# Power_Supply.net
KiCad netlist of a schematic drawn in Altium Designer
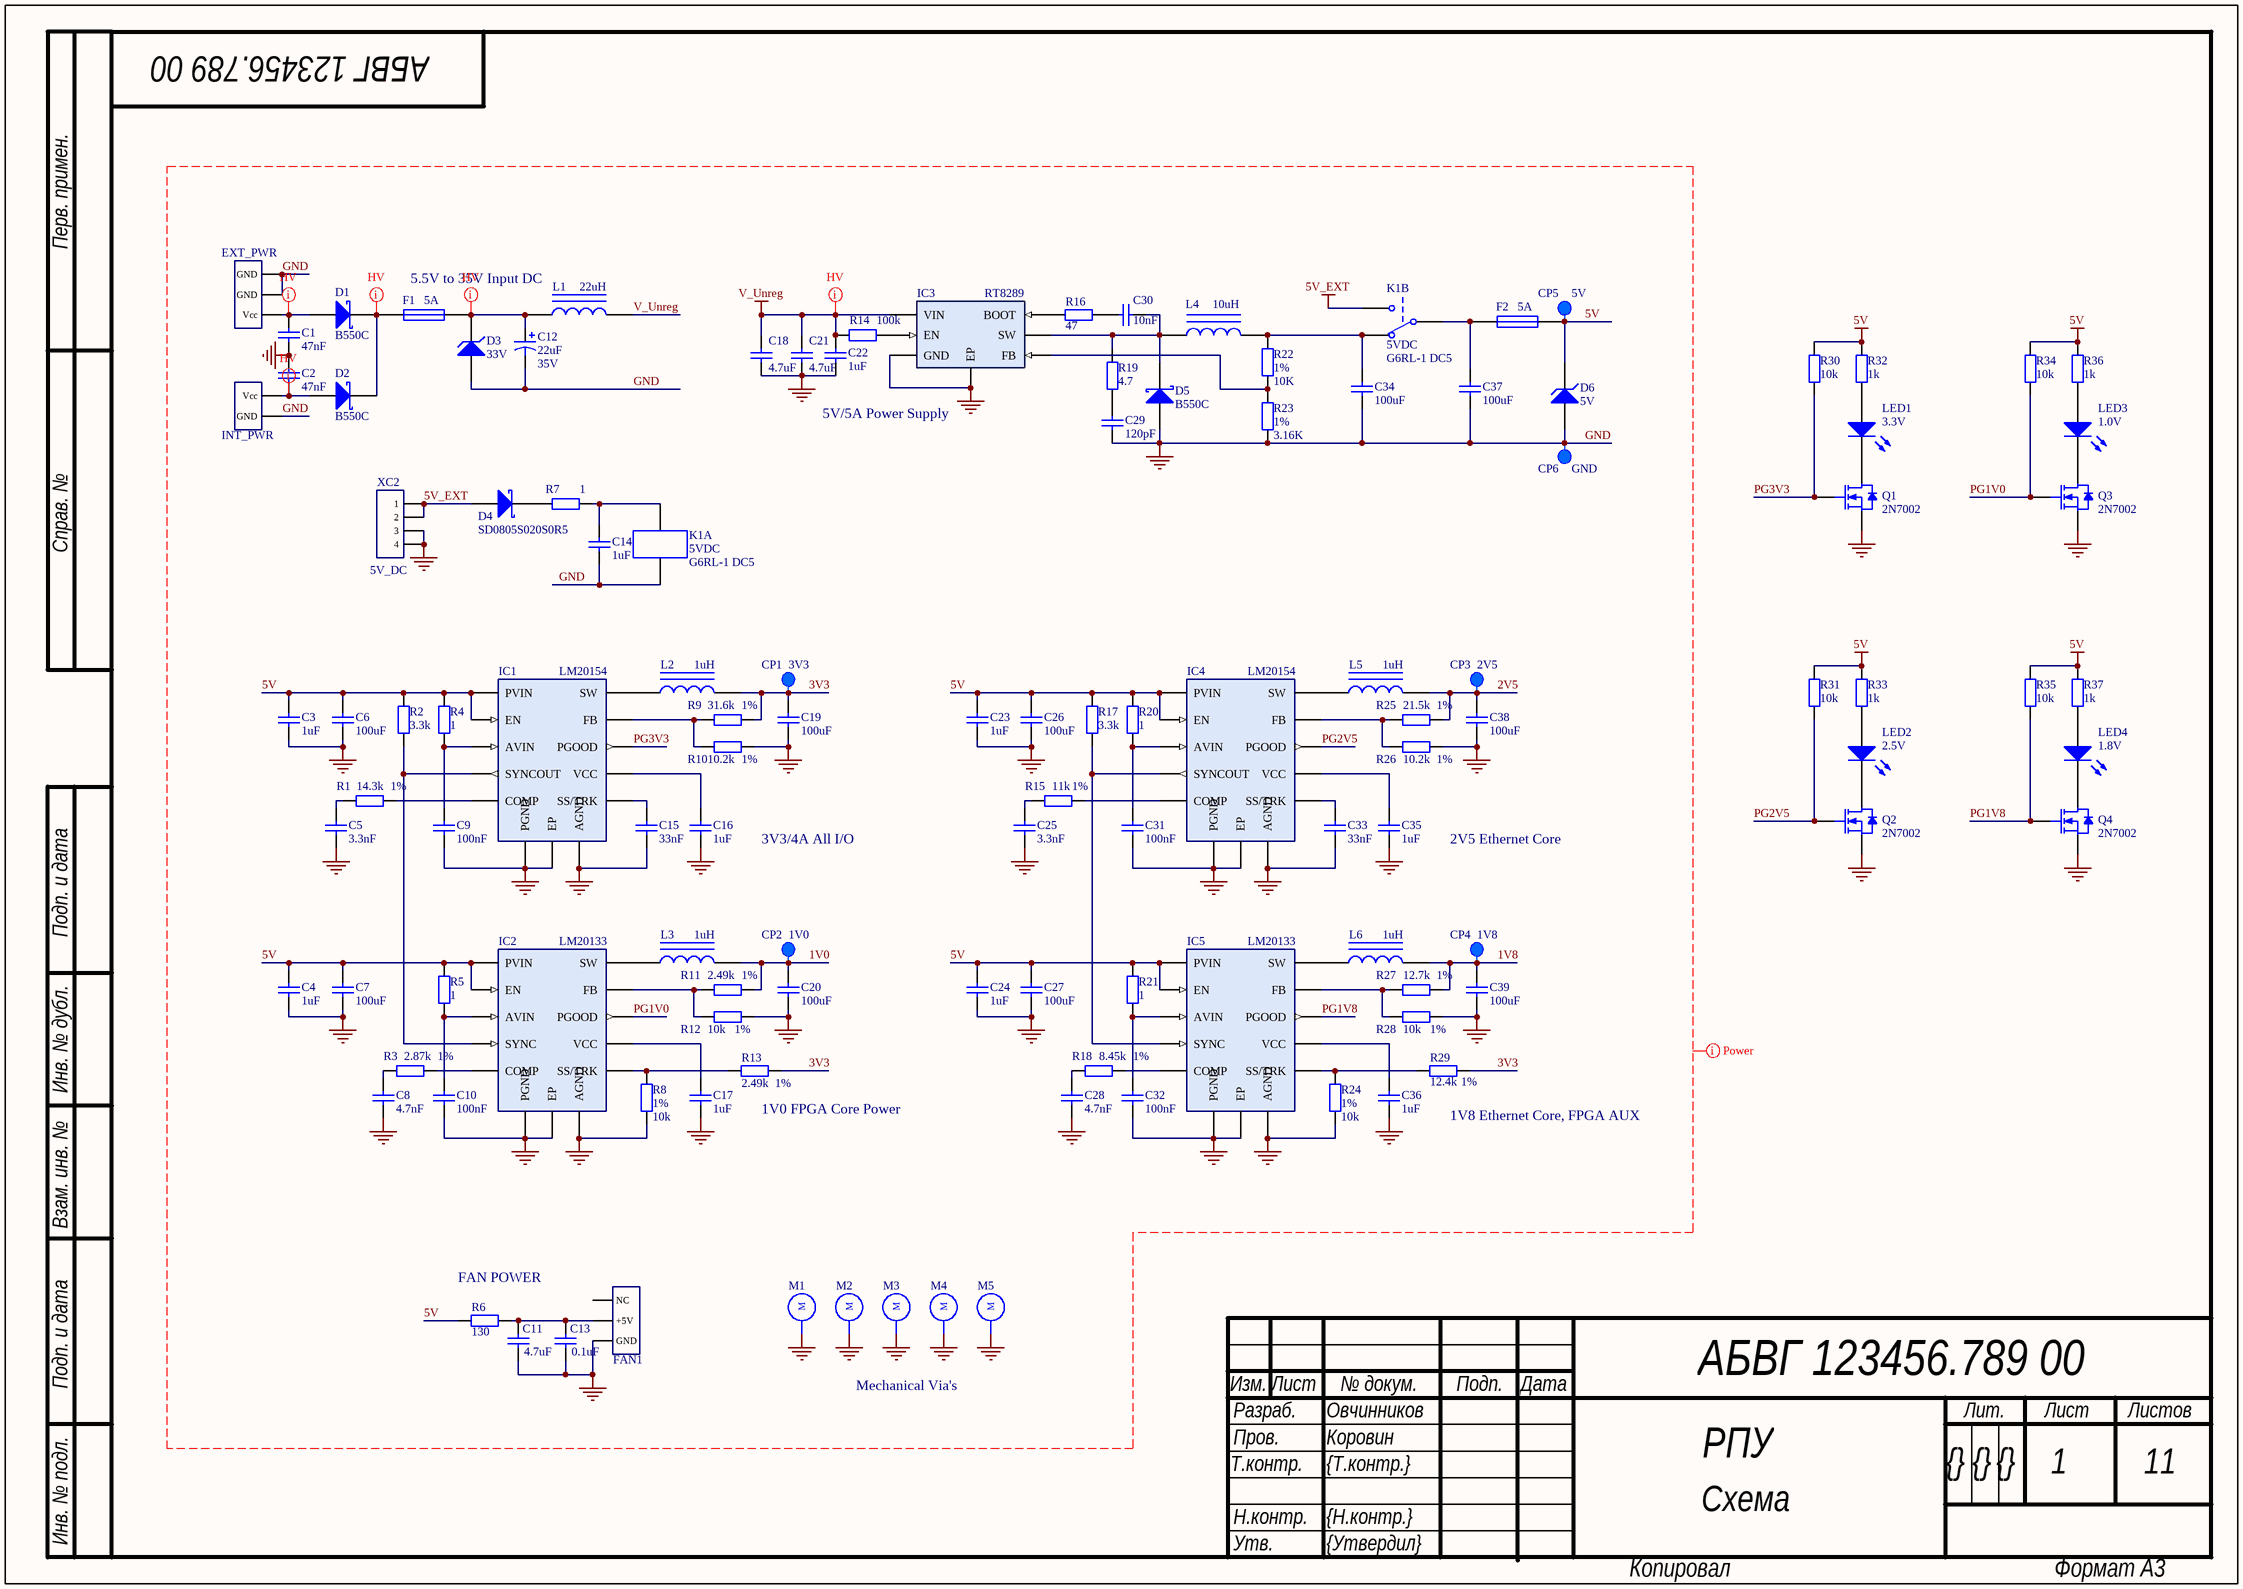
[diagram p0: Power_Supply.SchDoc]

(export (version "E")
  (design (tool "Eeschema 10.0.6"))
  (components
    (comp (ref "C1")
      (value "47nF")
      (footprint "C0805")
      (description "Cer Cap Small")
      (fields (field (name "MANUFACTURER") "Murata") (field (name "VOLTAGE") "50V"))
      (libsource (lib "USRP2_Clone") (part "Cer Cap"))
    )
    (comp (ref "C2")
      (value "47nF")
      (footprint "C0805")
      (description "Cer Cap Small")
      (fields (field (name "MANUFACTURER") "Murata") (field (name "VOLTAGE") "50V"))
      (libsource (lib "USRP2_Clone") (part "Cer Cap"))
    )
    (comp (ref "C3")
      (value "1uF")
      (footprint "C0805")
      (description "Cer Cap Small")
      (fields (field (name "MANUFACTURER") "Murata") (field (name "VOLTAGE") "16V"))
      (libsource (lib "USRP2_Clone") (part "Cer Cap"))
    )
    (comp (ref "C4")
      (value "1uF")
      (footprint "C0805")
      (description "Cer Cap Small")
      (fields (field (name "MANUFACTURER") "Murata") (field (name "VOLTAGE") "16V"))
      (libsource (lib "USRP2_Clone") (part "Cer Cap"))
    )
    (comp (ref "C5")
      (value "3.3nF")
      (footprint "C0603")
      (description "Cer Cap Small")
      (fields (field (name "MANUFACTURER") "Murata") (field (name "VOLTAGE") "25V"))
      (libsource (lib "USRP2_Clone") (part "Cer Cap"))
    )
    (comp (ref "C6")
      (value "100uF")
      (footprint "C1210")
      (description "Cer Cap Large")
      (fields (field (name "MANUFACTURER") "Murata") (field (name "TOLERANCE") "20%"))
      (libsource (lib "USRP2_Clone") (part "Cap uF"))
    )
    (comp (ref "C7")
      (value "100uF")
      (footprint "C1210")
      (description "Cer Cap Large")
      (fields (field (name "MANUFACTURER") "Murata") (field (name "TOLERANCE") "20%"))
      (libsource (lib "USRP2_Clone") (part "Cap uF"))
    )
    (comp (ref "C8")
      (value "4.7nF")
      (footprint "C0603")
      (description "Cer Cap Small")
      (fields (field (name "MANUFACTURER") "Murata") (field (name "VOLTAGE") "25V"))
      (libsource (lib "USRP2_Clone") (part "Cer Cap"))
    )
    (comp (ref "C9")
      (value "100nF")
      (footprint "C0603")
      (description "Cer Cap Small")
      (fields (field (name "MANUFACTURER") "Murata") (field (name "VOLTAGE") "16V"))
      (libsource (lib "USRP2_Clone") (part "Cer Cap"))
    )
    (comp (ref "C10")
      (value "100nF")
      (footprint "C0603")
      (description "Cer Cap Small")
      (fields (field (name "MANUFACTURER") "Murata") (field (name "VOLTAGE") "16V"))
      (libsource (lib "") (part "Cer Cap_1"))
    )
    (comp (ref "C11")
      (value "4.7uF")
      (footprint "C0805")
      (description "Cer Cap Small")
      (fields (field (name "MANUFACTURER") "Murata") (field (name "VOLTAGE") "16V"))
      (libsource (lib "USRP2_Clone") (part "Cer Cap"))
    )
    (comp (ref "C12")
      (value "22uF")
      (footprint "Tantalum_D")
      (description "Tantalum Polarity Cap")
      (fields
        (field (name "MANUFACTURER") "Tecap")
        (field (name "TOLERANCE") "20%")
        (field (name "VOLTAGE") "35V")
      )
      (libsource (lib "USRP2_Clone") (part "Tantalum Cap"))
    )
    (comp (ref "C13")
      (value "0.1uF")
      (footprint "C0805")
      (description "Cer Cap Small")
      (fields (field (name "MANUFACTURER") "Murata") (field (name "VOLTAGE") "16V"))
      (libsource (lib "USRP2_Clone") (part "Cer Cap"))
    )
    (comp (ref "C14")
      (value "1uF")
      (footprint "C0805")
      (description "Cer Cap Small")
      (fields (field (name "MANUFACTURER") "Murata") (field (name "VOLTAGE") "16V"))
      (libsource (lib "USRP2_Clone") (part "Cer Cap"))
    )
    (comp (ref "C15")
      (value "33nF")
      (footprint "C0603")
      (description "Cer Cap Small")
      (fields (field (name "MANUFACTURER") "Murata") (field (name "VOLTAGE") "25V"))
      (libsource (lib "") (part "Cer Cap_1"))
    )
    (comp (ref "C16")
      (value "1uF")
      (footprint "C0603")
      (description "Cer Cap Small")
      (fields (field (name "MANUFACTURER") "Murata") (field (name "VOLTAGE") "6.3V"))
      (libsource (lib "") (part "Cer Cap_1"))
    )
    (comp (ref "C17")
      (value "1uF")
      (footprint "C0603")
      (description "Cer Cap Small")
      (fields (field (name "MANUFACTURER") "Murata") (field (name "VOLTAGE") "6.3V"))
      (libsource (lib "") (part "Cer Cap_1"))
    )
    (comp (ref "C18")
      (value "4.7uF")
      (footprint "C1206")
      (description "Cer Cap Small")
      (fields (field (name "MANUFACTURER") "Murata") (field (name "VOLTAGE") "50V"))
      (libsource (lib "") (part "Cer Cap_1"))
    )
    (comp (ref "C19")
      (value "100uF")
      (footprint "C1210")
      (description "Cer Cap Large")
      (fields (field (name "MANUFACTURER") "Murata") (field (name "TOLERANCE") "20%"))
      (libsource (lib "USRP2_Clone") (part "Cap uF"))
    )
    (comp (ref "C20")
      (value "100uF")
      (footprint "C1210")
      (description "Cer Cap Large")
      (fields (field (name "MANUFACTURER") "Murata") (field (name "TOLERANCE") "20%"))
      (libsource (lib "USRP2_Clone") (part "Cap uF"))
    )
    (comp (ref "C21")
      (value "4.7uF")
      (footprint "C1206")
      (description "Cer Cap Small")
      (fields (field (name "MANUFACTURER") "Murata") (field (name "VOLTAGE") "50V"))
      (libsource (lib "") (part "Cer Cap_1"))
    )
    (comp (ref "C22")
      (value "1uF")
      (footprint "C1206")
      (description "Cer Cap Small")
      (fields (field (name "MANUFACTURER") "Murata") (field (name "VOLTAGE") "50V"))
      (libsource (lib "") (part "Cer Cap_1"))
    )
    (comp (ref "C23")
      (value "1uF")
      (footprint "C0805")
      (description "Cer Cap Small")
      (fields (field (name "MANUFACTURER") "Murata") (field (name "VOLTAGE") "16V"))
      (libsource (lib "") (part "Cer Cap_1"))
    )
    (comp (ref "C24")
      (value "1uF")
      (footprint "C0805")
      (description "Cer Cap Small")
      (fields (field (name "MANUFACTURER") "Murata") (field (name "VOLTAGE") "16V"))
      (libsource (lib "") (part "Cer Cap_1"))
    )
    (comp (ref "C25")
      (value "3.3nF")
      (footprint "C0603")
      (description "Cer Cap Small")
      (fields (field (name "MANUFACTURER") "Murata") (field (name "VOLTAGE") "25V"))
      (libsource (lib "USRP2_Clone") (part "Cer Cap"))
    )
    (comp (ref "C26")
      (value "100uF")
      (footprint "C1210")
      (description "Cer Cap Large")
      (fields (field (name "MANUFACTURER") "Murata") (field (name "TOLERANCE") "20%"))
      (libsource (lib "USRP2_Clone") (part "Cap uF"))
    )
    (comp (ref "C27")
      (value "100uF")
      (footprint "C1210")
      (description "Cer Cap Large")
      (fields (field (name "MANUFACTURER") "Murata") (field (name "TOLERANCE") "20%"))
      (libsource (lib "USRP2_Clone") (part "Cap uF"))
    )
    (comp (ref "C28")
      (value "4.7nF")
      (footprint "C0603")
      (description "Cer Cap Small")
      (fields (field (name "MANUFACTURER") "Murata") (field (name "VOLTAGE") "25V"))
      (libsource (lib "USRP2_Clone") (part "Cer Cap"))
    )
    (comp (ref "C29")
      (value "120pF")
      (footprint "C0805")
      (description "Cer Cap Small")
      (fields (field (name "MANUFACTURER") "Murata") (field (name "VOLTAGE") "50V"))
      (libsource (lib "USRP2_Clone") (part "Cer Cap"))
    )
    (comp (ref "C30")
      (value "10nF")
      (footprint "C0805")
      (description "Cer Cap Small")
      (fields (field (name "MANUFACTURER") "Murata") (field (name "VOLTAGE") "50V"))
      (libsource (lib "") (part "Cer Cap_1"))
    )
    (comp (ref "C31")
      (value "100nF")
      (footprint "C0603")
      (description "Cer Cap Small")
      (fields (field (name "MANUFACTURER") "Murata") (field (name "VOLTAGE") "16V"))
      (libsource (lib "") (part "Cer Cap_1"))
    )
    (comp (ref "C32")
      (value "100nF")
      (footprint "C0603")
      (description "Cer Cap Small")
      (fields (field (name "MANUFACTURER") "Murata") (field (name "VOLTAGE") "16V"))
      (libsource (lib "") (part "Cer Cap_1"))
    )
    (comp (ref "C33")
      (value "33nF")
      (footprint "C0603")
      (description "Cer Cap Small")
      (fields (field (name "MANUFACTURER") "Murata") (field (name "VOLTAGE") "25V"))
      (libsource (lib "USRP2_Clone") (part "Cer Cap"))
    )
    (comp (ref "C34")
      (value "100uF")
      (footprint "C1210")
      (description "Cer Cap Large")
      (fields (field (name "MANUFACTURER") "Murata") (field (name "TOLERANCE") "20%"))
      (libsource (lib "USRP2_Clone") (part "Cap uF"))
    )
    (comp (ref "C35")
      (value "1uF")
      (footprint "C0603")
      (description "Cer Cap Small")
      (fields (field (name "MANUFACTURER") "Murata") (field (name "VOLTAGE") "6.3V"))
      (libsource (lib "") (part "Cer Cap_1"))
    )
    (comp (ref "C36")
      (value "1uF")
      (footprint "C0603")
      (description "Cer Cap Small")
      (fields (field (name "MANUFACTURER") "Murata") (field (name "VOLTAGE") "6.3V"))
      (libsource (lib "") (part "Cer Cap_1"))
    )
    (comp (ref "C37")
      (value "100uF")
      (footprint "C1210")
      (description "Cer Cap Large")
      (fields (field (name "MANUFACTURER") "Murata") (field (name "TOLERANCE") "20%"))
      (libsource (lib "") (part "Cap uF_1"))
    )
    (comp (ref "C38")
      (value "100uF")
      (footprint "C1210")
      (description "Cer Cap Large")
      (fields (field (name "MANUFACTURER") "Murata") (field (name "TOLERANCE") "20%"))
      (libsource (lib "") (part "Cap uF_1"))
    )
    (comp (ref "C39")
      (value "100uF")
      (footprint "C1210")
      (description "Cer Cap Large")
      (fields (field (name "MANUFACTURER") "Murata") (field (name "TOLERANCE") "20%"))
      (libsource (lib "") (part "Cap uF_1"))
    )
    (comp (ref "CP1")
      (value "3V3")
      (footprint "Control Point")
      (description "Control Point")
      (libsource (lib "USRP2_Clone") (part "Control Point"))
    )
    (comp (ref "CP2")
      (value "1V0")
      (footprint "Control Point")
      (description "Control Point")
      (libsource (lib "USRP2_Clone") (part "Control Point"))
    )
    (comp (ref "CP3")
      (value "2V5")
      (footprint "Control Point")
      (description "Control Point")
      (libsource (lib "USRP2_Clone") (part "Control Point"))
    )
    (comp (ref "CP4")
      (value "1V8")
      (footprint "Control Point")
      (description "Control Point")
      (libsource (lib "USRP2_Clone") (part "Control Point"))
    )
    (comp (ref "CP5")
      (value "5V")
      (footprint "Control Point")
      (description "Control Point")
      (libsource (lib "USRP2_Clone") (part "Control Point"))
    )
    (comp (ref "CP6")
      (value "GND")
      (footprint "Control Point")
      (description "Control Point")
      (libsource (lib "USRP2_Clone") (part "Control Point"))
    )
    (comp (ref "D1")
      (value "B550C")
      (footprint "Diode_SMC")
      (description "Schottky Diode")
      (fields (field (name "NAME") "B550C"))
      (libsource (lib "USRP2_Clone") (part "B550C"))
    )
    (comp (ref "D2")
      (value "B550C")
      (footprint "Diode_SMC")
      (description "Schottky Diode")
      (fields (field (name "NAME") "B550C"))
      (libsource (lib "USRP2_Clone") (part "B550C"))
    )
    (comp (ref "D3")
      (value "Supressor")
      (footprint "SMF")
      (description "33V Supressor")
      (fields (field (name "POWER") "200W") (field (name "VOLTAGE") "33V"))
      (libsource (lib "USRP2_Clone") (part "Supressor"))
    )
    (comp (ref "D4")
      (value "D Schottky")
      (footprint "SD0805")
      (description "Schottky Diode SMD")
      (fields
        (field (name "VOLTAGE") "20V")
        (field (name "NAME") "SD0805S020S0R5")
        (field (name "MANUFACTURER") "AVX Corporation")
      )
      (libsource (lib "USRP2_Clone") (part "D Schottky"))
    )
    (comp (ref "D5")
      (value "B550C")
      (footprint "Diode_SMC")
      (description "Schottky Diode")
      (fields (field (name "NAME") "B550C"))
      (libsource (lib "USRP2_Clone") (part "B550C"))
    )
    (comp (ref "D6")
      (value "Supressor")
      (footprint "SMF")
      (fields (field (name "POWER") "200W") (field (name "VOLTAGE") "5V"))
      (libsource (lib "USRP2_Clone") (part "Supressor"))
    )
    (comp (ref "DC_PWR1")
      (value "EXT_PWR")
      (footprint "DC_CONNECTOR")
      (description "DC Power Connector 6mm")
      (fields (field (name "VOLTAGE") "12V"))
      (libsource (lib "USRP2_Clone") (part "DC_Connector"))
    )
    (comp (ref "F1")
      (value "Fuse")
      (footprint "Fuse")
      (description "Chip SMD Fuse")
      (fields (field (name "VOLTAGE") "125V") (field (name "CURRENT") "5A"))
      (libsource (lib "") (part "Fuse_1"))
    )
    (comp (ref "F2")
      (value "Fuse")
      (footprint "Fuse")
      (description "Chip SMD Fuse")
      (fields (field (name "VOLTAGE") "125V") (field (name "CURRENT") "5A"))
      (libsource (lib "USRP2_Clone") (part "Fuse"))
    )
    (comp (ref "FAN1")
      (value "FAN")
      (footprint "FAN_HDR")
      (description "FAN Connector")
      (fields (field (name "VOLTAGE") "12V"))
      (libsource (lib "USRP2_Clone") (part "FAN Connector"))
    )
    (comp (ref "IC1")
      (value "LM20154")
      (footprint "LM201xx")
      (description "Synchrous Buck Regulator")
      (libsource (lib "USRP2_Clone") (part "LM20154"))
    )
    (comp (ref "IC2")
      (value "LM20133")
      (footprint "LM201xx")
      (description "Synchronous Buck Regulator")
      (libsource (lib "USRP2_Clone") (part "LM20133"))
    )
    (comp (ref "IC3")
      (value "RT8289")
      (footprint "RT8289")
      (description "Step-Down Converter")
      (fields (field (name "VOLTAGE") "32V"))
      (libsource (lib "USRP2_Clone") (part "RT8289"))
    )
    (comp (ref "IC4")
      (value "LM20154")
      (footprint "LM201xx")
      (description "Synchrous Buck Regulator")
      (libsource (lib "USRP2_Clone") (part "LM20154"))
    )
    (comp (ref "IC5")
      (value "LM20133")
      (footprint "LM201xx")
      (description "Synchronous Buck Regulator")
      (libsource (lib "USRP2_Clone") (part "LM20133"))
    )
    (comp (ref "K1")
      (value "5VDC")
      (footprint "G6RL")
      (description "Single-Pole Dual-Throw Relay")
      (fields (field (name "MANUFACTURER") "Omron") (field (name "NAME") "G6RL-1 DC5"))
      (libsource (lib "USRP2_Clone") (part "Relay-SPDT_G6RL"))
    )
    (comp (ref "L1")
      (value "22uH")
      (footprint "XAL6060-223")
      (description "Magnetic-Core Inductor")
      (fields (field (name "TOLERANCE") "±30%") (field (name "MANUFACTURER") "Coilcraft"))
      (libsource (lib "USRP2_Clone") (part "Inductor Power"))
    )
    (comp (ref "L2")
      (value "1uH")
      (footprint "Coilcraft MSS1038")
      (description "Magnetic-Core Inductor")
      (fields (field (name "TOLERANCE") "±30%") (field (name "MANUFACTURER") "Coilcraft"))
      (libsource (lib "USRP2_Clone") (part "Inductor Power"))
    )
    (comp (ref "L3")
      (value "1uH")
      (footprint "Coilcraft MSS1038")
      (description "Magnetic-Core Inductor")
      (fields (field (name "TOLERANCE") "±30%") (field (name "MANUFACTURER") "Coilcraft"))
      (libsource (lib "USRP2_Clone") (part "Inductor Power"))
    )
    (comp (ref "L4")
      (value "10uH")
      (footprint "Coilcraft MSS1048")
      (description "Magnetic-Core Inductor")
      (fields (field (name "TOLERANCE") "±30%") (field (name "MANUFACTURER") "Coilcraft"))
      (libsource (lib "USRP2_Clone") (part "Inductor Power"))
    )
    (comp (ref "L5")
      (value "1uH")
      (footprint "Coilcraft MSS1038")
      (description "Magnetic-Core Inductor")
      (fields (field (name "TOLERANCE") "±30%") (field (name "MANUFACTURER") "Coilcraft"))
      (libsource (lib "USRP2_Clone") (part "Inductor Power"))
    )
    (comp (ref "L6")
      (value "1uH")
      (footprint "Coilcraft MSS1038")
      (description "Magnetic-Core Inductor")
      (fields (field (name "TOLERANCE") "±30%") (field (name "MANUFACTURER") "Coilcraft"))
      (libsource (lib "USRP2_Clone") (part "Inductor Power"))
    )
    (comp (ref "LED1")
      (value "3.3V")
      (footprint "LED_0402_Blue")
      (description "Typical RED, GREEN, YELLOW, AMBER GaAs LED")
      (fields (field (name "MANUFACTURER") "Kingbright"))
      (libsource (lib "USRP2_Clone") (part "LED"))
    )
    (comp (ref "LED2")
      (value "2.5V")
      (footprint "LED_0402_Blue")
      (description "Typical RED, GREEN, YELLOW, AMBER GaAs LED")
      (fields (field (name "MANUFACTURER") "Kingbright"))
      (libsource (lib "USRP2_Clone") (part "LED"))
    )
    (comp (ref "LED3")
      (value "1.0V")
      (footprint "LED_0402_Blue")
      (description "Typical RED, GREEN, YELLOW, AMBER GaAs LED")
      (fields (field (name "MANUFACTURER") "Kingbright"))
      (libsource (lib "USRP2_Clone") (part "LED"))
    )
    (comp (ref "LED4")
      (value "1.8V")
      (footprint "LED_0402_Blue")
      (description "Typical RED, GREEN, YELLOW, AMBER GaAs LED")
      (fields (field (name "MANUFACTURER") "Kingbright"))
      (libsource (lib "USRP2_Clone") (part "LED"))
    )
    (comp (ref "M1")
      (value "Via")
      (footprint "Mechanical_Via")
      (description "Mechanical Via")
      (libsource (lib "USRP2_Clone") (part "Mechanical_Via"))
    )
    (comp (ref "M2")
      (value "Via")
      (footprint "Mechanical_Via")
      (description "Mechanical Via")
      (libsource (lib "USRP2_Clone") (part "Mechanical_Via"))
    )
    (comp (ref "M3")
      (value "Via")
      (footprint "Mechanical_Via")
      (description "Mechanical Via")
      (libsource (lib "USRP2_Clone") (part "Mechanical_Via"))
    )
    (comp (ref "M4")
      (value "Via")
      (footprint "Mechanical_Via")
      (description "Mechanical Via")
      (libsource (lib "USRP2_Clone") (part "Mechanical_Via"))
    )
    (comp (ref "M5")
      (value "Via")
      (footprint "Mechanical_Via")
      (description "Mechanical Via")
      (libsource (lib "USRP2_Clone") (part "Mechanical_Via"))
    )
    (comp (ref "Q1")
      (value "2N7002")
      (footprint "SOT-23")
      (description "N-Channel MOSFET 2N7002")
      (fields (field (name "VOLTAGE") "60V"))
      (libsource (lib "USRP2_Clone") (part "2N7002"))
    )
    (comp (ref "Q2")
      (value "2N7002")
      (footprint "SOT-23")
      (description "N-Channel MOSFET 2N7002")
      (fields (field (name "VOLTAGE") "60V"))
      (libsource (lib "USRP2_Clone") (part "2N7002"))
    )
    (comp (ref "Q3")
      (value "2N7002")
      (footprint "SOT-23")
      (description "N-Channel MOSFET 2N7002")
      (fields (field (name "VOLTAGE") "60V"))
      (libsource (lib "USRP2_Clone") (part "2N7002"))
    )
    (comp (ref "Q4")
      (value "2N7002")
      (footprint "SOT-23")
      (description "N-Channel MOSFET 2N7002")
      (fields (field (name "VOLTAGE") "60V"))
      (libsource (lib "USRP2_Clone") (part "2N7002"))
    )
    (comp (ref "R1")
      (value "14.3k")
      (footprint "R0603")
      (description "Resistor")
      (fields
        (field (name "TOLERANCE") "1%")
        (field (name "POWER") "0.062 Wt")
        (field (name "Comment") "Res")
      )
      (libsource (lib "") (part "Res_2"))
    )
    (comp (ref "R2")
      (value "3.3k")
      (footprint "R0603")
      (description "Resistor")
      (fields (field (name "TOLERANCE") "5%") (field (name "POWER") "0.062 Wt"))
      (libsource (lib "") (part "Res_5"))
    )
    (comp (ref "R3")
      (value "2.87k")
      (footprint "R0603")
      (description "Resistor")
      (fields
        (field (name "TOLERANCE") "1%")
        (field (name "POWER") "0.062 Wt")
        (field (name "Comment") "Res")
      )
      (libsource (lib "") (part "Res_2"))
    )
    (comp (ref "R4")
      (value "1")
      (footprint "R0603")
      (description "Resistor")
      (fields (field (name "TOLERANCE") "5%") (field (name "POWER") "0.062 Wt"))
      (libsource (lib "USRP2_Clone") (part "Res"))
    )
    (comp (ref "R5")
      (value "1")
      (footprint "R0603")
      (description "Resistor")
      (fields (field (name "TOLERANCE") "5%") (field (name "POWER") "0.062 Wt"))
      (libsource (lib "USRP2_Clone") (part "Res"))
    )
    (comp (ref "R6")
      (value "130")
      (footprint "R0805")
      (description "Resistor")
      (fields (field (name "TOLERANCE") "5%") (field (name "POWER") "0.062 Wt"))
      (libsource (lib "") (part "Res_4"))
    )
    (comp (ref "R7")
      (value "1")
      (footprint "R0805")
      (description "Resistor")
      (fields (field (name "TOLERANCE") "5%") (field (name "POWER") "0.062 Wt"))
      (libsource (lib "") (part "Res_4"))
    )
    (comp (ref "R8")
      (value "10k")
      (footprint "R0603")
      (description "Resistor")
      (fields
        (field (name "TOLERANCE") "1%")
        (field (name "POWER") "0.062 Wt")
        (field (name "Comment") "Res")
      )
      (libsource (lib "") (part "Res_5"))
    )
    (comp (ref "R9")
      (value "31.6k")
      (footprint "R0603")
      (description "Resistor")
      (fields
        (field (name "TOLERANCE") "1%")
        (field (name "POWER") "0.062 Wt")
        (field (name "Comment") "Res")
      )
      (libsource (lib "") (part "Res_1"))
    )
    (comp (ref "R10")
      (value "10.2k")
      (footprint "R0603")
      (description "Resistor")
      (fields
        (field (name "TOLERANCE") "1%")
        (field (name "POWER") "0.062 Wt")
        (field (name "Comment") "Res")
      )
      (libsource (lib "") (part "Res_2"))
    )
    (comp (ref "R11")
      (value "2.49k")
      (footprint "R0603")
      (description "Resistor")
      (fields
        (field (name "TOLERANCE") "1%")
        (field (name "POWER") "0.062 Wt")
        (field (name "Comment") "Res")
      )
      (libsource (lib "") (part "Res_1"))
    )
    (comp (ref "R12")
      (value "10k")
      (footprint "R0603")
      (description "Resistor")
      (fields
        (field (name "TOLERANCE") "1%")
        (field (name "POWER") "0.062 Wt")
        (field (name "Comment") "Res")
      )
      (libsource (lib "") (part "Res_2"))
    )
    (comp (ref "R13")
      (value "2.49k")
      (footprint "R0603")
      (description "Resistor")
      (fields
        (field (name "TOLERANCE") "1%")
        (field (name "POWER") "0.062 Wt")
        (field (name "Comment") "Res")
      )
      (libsource (lib "") (part "Res_1"))
    )
    (comp (ref "R14")
      (value "100k")
      (footprint "R0805")
      (description "Resistor")
      (fields (field (name "TOLERANCE") "5%") (field (name "POWER") "0.062 Wt"))
      (libsource (lib "") (part "Res_1"))
    )
    (comp (ref "R15")
      (value "11k")
      (footprint "R0603")
      (description "Resistor")
      (fields
        (field (name "TOLERANCE") "1%")
        (field (name "POWER") "0.062 Wt")
        (field (name "Comment") "Res")
      )
      (libsource (lib "") (part "Res_2"))
    )
    (comp (ref "R16")
      (value "47")
      (footprint "R0805")
      (description "Resistor")
      (fields (field (name "TOLERANCE") "5%") (field (name "POWER") "0.062 Wt"))
      (libsource (lib "") (part "Res_6"))
    )
    (comp (ref "R17")
      (value "3.3k")
      (footprint "R0603")
      (description "Resistor")
      (fields (field (name "TOLERANCE") "5%") (field (name "POWER") "0.062 Wt"))
      (libsource (lib "") (part "Res_7"))
    )
    (comp (ref "R18")
      (value "8.45k")
      (footprint "R0603")
      (description "Resistor")
      (fields
        (field (name "TOLERANCE") "1%")
        (field (name "POWER") "0.062 Wt")
        (field (name "Comment") "Res")
      )
      (libsource (lib "") (part "Res_2"))
    )
    (comp (ref "R19")
      (value "4.7")
      (footprint "R0805")
      (description "Resistor")
      (fields (field (name "TOLERANCE") "5%") (field (name "POWER") "0.062 Wt"))
      (libsource (lib "USRP2_Clone") (part "Res"))
    )
    (comp (ref "R20")
      (value "1")
      (footprint "R0603")
      (description "Resistor")
      (fields (field (name "TOLERANCE") "5%") (field (name "POWER") "0.062 Wt"))
      (libsource (lib "USRP2_Clone") (part "Res"))
    )
    (comp (ref "R21")
      (value "1")
      (footprint "R0603")
      (description "Resistor")
      (fields (field (name "TOLERANCE") "5%") (field (name "POWER") "0.062 Wt"))
      (libsource (lib "USRP2_Clone") (part "Res"))
    )
    (comp (ref "R22")
      (value "10K")
      (footprint "R0805")
      (description "Resistor")
      (fields
        (field (name "TOLERANCE") "1%")
        (field (name "POWER") "0.062 Wt")
        (field (name "Comment") "Res")
      )
      (libsource (lib "") (part "Res_3"))
    )
    (comp (ref "R23")
      (value "3.16K")
      (footprint "R0805")
      (description "Resistor")
      (fields
        (field (name "TOLERANCE") "1%")
        (field (name "POWER") "0.062 Wt")
        (field (name "Comment") "Res")
      )
      (libsource (lib "") (part "Res_3"))
    )
    (comp (ref "R24")
      (value "10k")
      (footprint "R0603")
      (description "Resistor")
      (fields
        (field (name "TOLERANCE") "1%")
        (field (name "POWER") "0.062 Wt")
        (field (name "Comment") "Res")
      )
      (libsource (lib "") (part "Res_5"))
    )
    (comp (ref "R25")
      (value "21.5k")
      (footprint "R0603")
      (description "Resistor")
      (fields
        (field (name "TOLERANCE") "1%")
        (field (name "POWER") "0.062 Wt")
        (field (name "Comment") "Res")
      )
      (libsource (lib "") (part "Res_1"))
    )
    (comp (ref "R26")
      (value "10.2k")
      (footprint "R0603")
      (description "Resistor")
      (fields
        (field (name "TOLERANCE") "1%")
        (field (name "POWER") "0.062 Wt")
        (field (name "Comment") "Res")
      )
      (libsource (lib "") (part "Res_2"))
    )
    (comp (ref "R27")
      (value "12.7k")
      (footprint "R0603")
      (description "Resistor")
      (fields
        (field (name "TOLERANCE") "1%")
        (field (name "POWER") "0.062 Wt")
        (field (name "Comment") "Res")
      )
      (libsource (lib "") (part "Res_1"))
    )
    (comp (ref "R28")
      (value "10k")
      (footprint "R0603")
      (description "Resistor")
      (fields
        (field (name "TOLERANCE") "1%")
        (field (name "POWER") "0.062 Wt")
        (field (name "Comment") "Res")
      )
      (libsource (lib "") (part "Res_2"))
    )
    (comp (ref "R29")
      (value "12.4k")
      (footprint "R0603")
      (description "Resistor")
      (fields
        (field (name "TOLERANCE") "1%")
        (field (name "POWER") "0.062 Wt")
        (field (name "Comment") "Res")
      )
      (libsource (lib "") (part "Res_1"))
    )
    (comp (ref "R30")
      (value "10k")
      (footprint "R0402")
      (description "Resistor")
      (fields (field (name "TOLERANCE") "5%") (field (name "POWER") "0.062 Wt"))
      (libsource (lib "") (part "Res_3"))
    )
    (comp (ref "R31")
      (value "10k")
      (footprint "R0402")
      (description "Resistor")
      (fields (field (name "TOLERANCE") "5%") (field (name "POWER") "0.062 Wt"))
      (libsource (lib "") (part "Res_3"))
    )
    (comp (ref "R32")
      (value "1k")
      (footprint "R0402")
      (description "Resistor")
      (fields (field (name "TOLERANCE") "5%") (field (name "POWER") "0.062 Wt"))
      (libsource (lib "") (part "Res_3"))
    )
    (comp (ref "R33")
      (value "1k")
      (footprint "R0402")
      (description "Resistor")
      (fields (field (name "TOLERANCE") "5%") (field (name "POWER") "0.062 Wt"))
      (libsource (lib "") (part "Res_3"))
    )
    (comp (ref "R34")
      (value "10k")
      (footprint "R0402")
      (description "Resistor")
      (fields (field (name "TOLERANCE") "5%") (field (name "POWER") "0.062 Wt"))
      (libsource (lib "") (part "Res_3"))
    )
    (comp (ref "R35")
      (value "10k")
      (footprint "R0402")
      (description "Resistor")
      (fields (field (name "TOLERANCE") "5%") (field (name "POWER") "0.062 Wt"))
      (libsource (lib "") (part "Res_3"))
    )
    (comp (ref "R36")
      (value "1k")
      (footprint "R0402")
      (description "Resistor")
      (fields (field (name "TOLERANCE") "5%") (field (name "POWER") "0.062 Wt"))
      (libsource (lib "") (part "Res_3"))
    )
    (comp (ref "R37")
      (value "1k")
      (footprint "R0402")
      (description "Resistor")
      (fields (field (name "TOLERANCE") "5%") (field (name "POWER") "0.062 Wt"))
      (libsource (lib "") (part "Res_3"))
    )
    (comp (ref "XC1")
      (value "INT_PWR")
      (footprint "2x2 PWR_HDR")
      (description "Power Connector Mini-Fit")
      (fields (field (name "VOLTAGE") "12V"))
      (libsource (lib "USRP2_Clone") (part "1x2 Pwr_Hdr"))
    )
    (comp (ref "XC2")
      (value "5V_DC")
      (footprint "H-DAC 64")
      (fields
        (field (name "VOLTAGE") "500V")
        (field (name "MANUFACTURER") "Molex")
        (field (name "PART NUMBER") "0311010040")
      )
      (libsource (lib "USRP2_Clone") (part "H-DAC PCB Connector"))
    )
  )
  (nets
    (net (code "1") (name "/1V0") (class "Default")
      (node (ref "C20") (pin "1") (pinfunction "1_1") (pintype "passive"))
      (node (ref "CP2") (pin "1") (pinfunction "1_1") (pintype "passive"))
      (node (ref "L3") (pin "2") (pinfunction "2_2") (pintype "passive"))
      (node (ref "R11") (pin "1") (pinfunction "1_1") (pintype "passive"))
    )
    (net (code "2") (name "/1V8") (class "Default")
      (node (ref "C39") (pin "2") (pinfunction "2_2") (pintype "passive"))
      (node (ref "CP4") (pin "1") (pinfunction "1_1") (pintype "passive"))
      (node (ref "L6") (pin "2") (pinfunction "2_2") (pintype "passive"))
      (node (ref "R27") (pin "1") (pinfunction "1_1") (pintype "passive"))
    )
    (net (code "3") (name "/2V5") (class "Default")
      (node (ref "C38") (pin "2") (pinfunction "2_2") (pintype "passive"))
      (node (ref "CP3") (pin "1") (pinfunction "1_1") (pintype "passive"))
      (node (ref "L5") (pin "2") (pinfunction "2_2") (pintype "passive"))
      (node (ref "R25") (pin "1") (pinfunction "1_1") (pintype "passive"))
    )
    (net (code "4") (name "/3V3") (class "Default")
      (node (ref "C19") (pin "1") (pinfunction "1_1") (pintype "passive"))
      (node (ref "CP1") (pin "1") (pinfunction "1_1") (pintype "passive"))
      (node (ref "L2") (pin "2") (pinfunction "2_2") (pintype "passive"))
      (node (ref "R13") (pin "1") (pinfunction "1_1") (pintype "passive"))
      (node (ref "R29") (pin "1") (pinfunction "1_1") (pintype "passive"))
      (node (ref "R9") (pin "1") (pinfunction "1_1") (pintype "passive"))
    )
    (net (code "5") (name "/PG1V0") (class "Default")
      (node (ref "IC2") (pin "3") (pinfunction "PGOOD_3") (pintype "output"))
      (node (ref "Q3") (pin "1") (pinfunction "G_1") (pintype "passive"))
      (node (ref "R34") (pin "1") (pinfunction "1_1") (pintype "passive"))
    )
    (net (code "6") (name "/PG1V8") (class "Default")
      (node (ref "IC5") (pin "3") (pinfunction "PGOOD_3") (pintype "output"))
      (node (ref "Q4") (pin "1") (pinfunction "G_1") (pintype "passive"))
      (node (ref "R35") (pin "1") (pinfunction "1_1") (pintype "passive"))
    )
    (net (code "7") (name "/PG2V5") (class "Default")
      (node (ref "IC4") (pin "3") (pinfunction "PGOOD_3") (pintype "output"))
      (node (ref "Q2") (pin "1") (pinfunction "G_1") (pintype "passive"))
      (node (ref "R31") (pin "1") (pinfunction "1_1") (pintype "passive"))
    )
    (net (code "8") (name "/PG3V3") (class "Default")
      (node (ref "IC1") (pin "3") (pinfunction "PGOOD_3") (pintype "output"))
      (node (ref "Q1") (pin "1") (pinfunction "G_1") (pintype "passive"))
      (node (ref "R30") (pin "1") (pinfunction "1_1") (pintype "passive"))
    )
    (net (code "9") (name "5V") (class "Default")
      (node (ref "C23") (pin "1") (pinfunction "1_1") (pintype "passive"))
      (node (ref "C24") (pin "2") (pinfunction "2_2") (pintype "passive"))
      (node (ref "C26") (pin "1") (pinfunction "1_1") (pintype "passive"))
      (node (ref "C27") (pin "1") (pinfunction "1_1") (pintype "passive"))
      (node (ref "C3") (pin "1") (pinfunction "1_1") (pintype "passive"))
      (node (ref "C4") (pin "1") (pinfunction "1_1") (pintype "passive"))
      (node (ref "C6") (pin "1") (pinfunction "1_1") (pintype "passive"))
      (node (ref "C7") (pin "1") (pinfunction "1_1") (pintype "passive"))
      (node (ref "CP5") (pin "1") (pinfunction "1_1") (pintype "passive"))
      (node (ref "D6") (pin "1") (pinfunction "K_1") (pintype "passive"))
      (node (ref "F2") (pin "1") (pinfunction "1_1") (pintype "passive"))
      (node (ref "IC1") (pin "12") (pinfunction "EN_12") (pintype "input"))
      (node (ref "IC1") (pin "6") (pinfunction "PVIN_6") (pintype "passive"))
      (node (ref "IC2") (pin "12") (pinfunction "EN_12") (pintype "input"))
      (node (ref "IC2") (pin "6") (pinfunction "PVIN_6") (pintype "passive"))
      (node (ref "IC4") (pin "12") (pinfunction "EN_12") (pintype "input"))
      (node (ref "IC4") (pin "6") (pinfunction "PVIN_6") (pintype "passive"))
      (node (ref "IC5") (pin "12") (pinfunction "EN_12") (pintype "input"))
      (node (ref "IC5") (pin "6") (pinfunction "PVIN_6") (pintype "passive"))
      (node (ref "R17") (pin "1") (pinfunction "1_1") (pintype "passive"))
      (node (ref "R2") (pin "2") (pinfunction "2_2") (pintype "passive"))
      (node (ref "R20") (pin "1") (pinfunction "1_1") (pintype "passive"))
      (node (ref "R21") (pin "1") (pinfunction "1_1") (pintype "passive"))
      (node (ref "R30") (pin "2") (pinfunction "2_2") (pintype "passive"))
      (node (ref "R31") (pin "2") (pinfunction "2_2") (pintype "passive"))
      (node (ref "R32") (pin "2") (pinfunction "2_2") (pintype "passive"))
      (node (ref "R33") (pin "2") (pinfunction "2_2") (pintype "passive"))
      (node (ref "R34") (pin "2") (pinfunction "2_2") (pintype "passive"))
      (node (ref "R35") (pin "2") (pinfunction "2_2") (pintype "passive"))
      (node (ref "R36") (pin "2") (pinfunction "2_2") (pintype "passive"))
      (node (ref "R37") (pin "2") (pinfunction "2_2") (pintype "passive"))
      (node (ref "R4") (pin "1") (pinfunction "1_1") (pintype "passive"))
      (node (ref "R5") (pin "1") (pinfunction "1_1") (pintype "passive"))
      (node (ref "R6") (pin "2") (pinfunction "2_2") (pintype "passive"))
    )
    (net (code "10") (name "5V_EXT") (class "Default")
      (node (ref "D4") (pin "2") (pinfunction "A_2") (pintype "passive"))
      (node (ref "K1") (pin "3") (pinfunction "3_3") (pintype "passive"))
      (node (ref "XC2") (pin "1") (pinfunction "1_1") (pintype "passive"))
      (node (ref "XC2") (pin "2") (pinfunction "2_2") (pintype "passive"))
    )
    (net (code "11") (name "GND") (class "Default")
      (node (ref "C1") (pin "1") (pinfunction "1_1") (pintype "passive"))
      (node (ref "C10") (pin "2") (pinfunction "2_2") (pintype "passive"))
      (node (ref "C11") (pin "2") (pinfunction "2_2") (pintype "passive"))
      (node (ref "C12") (pin "2") (pinfunction "2_2") (pintype "passive"))
      (node (ref "C13") (pin "2") (pinfunction "2_2") (pintype "passive"))
      (node (ref "C14") (pin "2") (pinfunction "2_2") (pintype "passive"))
      (node (ref "C15") (pin "1") (pinfunction "1_1") (pintype "passive"))
      (node (ref "C16") (pin "1") (pinfunction "1_1") (pintype "passive"))
      (node (ref "C17") (pin "1") (pinfunction "1_1") (pintype "passive"))
      (node (ref "C18") (pin "2") (pinfunction "2_2") (pintype "passive"))
      (node (ref "C19") (pin "2") (pinfunction "2_2") (pintype "passive"))
      (node (ref "C2") (pin "2") (pinfunction "2_2") (pintype "passive"))
      (node (ref "C20") (pin "2") (pinfunction "2_2") (pintype "passive"))
      (node (ref "C21") (pin "2") (pinfunction "2_2") (pintype "passive"))
      (node (ref "C22") (pin "2") (pinfunction "2_2") (pintype "passive"))
      (node (ref "C23") (pin "2") (pinfunction "2_2") (pintype "passive"))
      (node (ref "C24") (pin "1") (pinfunction "1_1") (pintype "passive"))
      (node (ref "C25") (pin "2") (pinfunction "2_2") (pintype "passive"))
      (node (ref "C26") (pin "2") (pinfunction "2_2") (pintype "passive"))
      (node (ref "C27") (pin "2") (pinfunction "2_2") (pintype "passive"))
      (node (ref "C28") (pin "2") (pinfunction "2_2") (pintype "passive"))
      (node (ref "C29") (pin "1") (pinfunction "1_1") (pintype "passive"))
      (node (ref "C3") (pin "2") (pinfunction "2_2") (pintype "passive"))
      (node (ref "C31") (pin "2") (pinfunction "2_2") (pintype "passive"))
      (node (ref "C32") (pin "2") (pinfunction "2_2") (pintype "passive"))
      (node (ref "C33") (pin "2") (pinfunction "2_2") (pintype "passive"))
      (node (ref "C34") (pin "2") (pinfunction "2_2") (pintype "passive"))
      (node (ref "C35") (pin "1") (pinfunction "1_1") (pintype "passive"))
      (node (ref "C36") (pin "1") (pinfunction "1_1") (pintype "passive"))
      (node (ref "C37") (pin "1") (pinfunction "1_1") (pintype "passive"))
      (node (ref "C38") (pin "1") (pinfunction "1_1") (pintype "passive"))
      (node (ref "C39") (pin "1") (pinfunction "1_1") (pintype "passive"))
      (node (ref "C4") (pin "2") (pinfunction "2_2") (pintype "passive"))
      (node (ref "C5") (pin "2") (pinfunction "2_2") (pintype "passive"))
      (node (ref "C6") (pin "2") (pinfunction "2_2") (pintype "passive"))
      (node (ref "C7") (pin "2") (pinfunction "2_2") (pintype "passive"))
      (node (ref "C8") (pin "2") (pinfunction "2_2") (pintype "passive"))
      (node (ref "C9") (pin "1") (pinfunction "1_1") (pintype "passive"))
      (node (ref "CP6") (pin "1") (pinfunction "1_1") (pintype "passive"))
      (node (ref "D3") (pin "2") (pinfunction "A_2") (pintype "passive"))
      (node (ref "D5") (pin "2") (pinfunction "A_2") (pintype "passive"))
      (node (ref "D6") (pin "2") (pinfunction "A_2") (pintype "passive"))
      (node (ref "DC_PWR1") (pin "2") (pinfunction "GND_2") (pintype "passive"))
      (node (ref "DC_PWR1") (pin "3") (pinfunction "GND_3") (pintype "passive"))
      (node (ref "FAN1") (pin "1") (pinfunction "GND_1") (pintype "passive"))
      (node (ref "IC1") (pin "10") (pinfunction "PGND_10") (pintype "passive"))
      (node (ref "IC1") (pin "15") (pinfunction "AGND_15") (pintype "passive"))
      (node (ref "IC1") (pin "17") (pinfunction "EP_17") (pintype "passive"))
      (node (ref "IC2") (pin "10") (pinfunction "PGND_10") (pintype "passive"))
      (node (ref "IC2") (pin "15") (pinfunction "AGND_15") (pintype "passive"))
      (node (ref "IC2") (pin "17") (pinfunction "EP_17") (pintype "passive"))
      (node (ref "IC3") (pin "6") (pinfunction "GND_6") (pintype "power_in"))
      (node (ref "IC3") (pin "9") (pinfunction "EP_9") (pintype "passive"))
      (node (ref "IC4") (pin "10") (pinfunction "PGND_10") (pintype "passive"))
      (node (ref "IC4") (pin "15") (pinfunction "AGND_15") (pintype "passive"))
      (node (ref "IC4") (pin "17") (pinfunction "EP_17") (pintype "passive"))
      (node (ref "IC5") (pin "10") (pinfunction "PGND_10") (pintype "passive"))
      (node (ref "IC5") (pin "15") (pinfunction "AGND_15") (pintype "passive"))
      (node (ref "IC5") (pin "17") (pinfunction "EP_17") (pintype "passive"))
      (node (ref "K1") (pin "1") (pinfunction "1_1") (pintype "passive"))
      (node (ref "M1") (pin "0") (pinfunction "M_0") (pintype "passive"))
      (node (ref "M2") (pin "0") (pinfunction "M_0") (pintype "passive"))
      (node (ref "M3") (pin "0") (pinfunction "M_0") (pintype "passive"))
      (node (ref "M4") (pin "0") (pinfunction "M_0") (pintype "passive"))
      (node (ref "M5") (pin "0") (pinfunction "M_0") (pintype "passive"))
      (node (ref "Q1") (pin "2") (pinfunction "S_2") (pintype "passive"))
      (node (ref "Q2") (pin "2") (pinfunction "S_2") (pintype "passive"))
      (node (ref "Q3") (pin "2") (pinfunction "S_2") (pintype "passive"))
      (node (ref "Q4") (pin "2") (pinfunction "S_2") (pintype "passive"))
      (node (ref "R10") (pin "2") (pinfunction "2_2") (pintype "passive"))
      (node (ref "R12") (pin "2") (pinfunction "2_2") (pintype "passive"))
      (node (ref "R23") (pin "1") (pinfunction "1_1") (pintype "passive"))
      (node (ref "R24") (pin "1") (pinfunction "1_1") (pintype "passive"))
      (node (ref "R26") (pin "2") (pinfunction "2_2") (pintype "passive"))
      (node (ref "R28") (pin "2") (pinfunction "2_2") (pintype "passive"))
      (node (ref "R8") (pin "1") (pinfunction "1_1") (pintype "passive"))
      (node (ref "XC1") (pin "1") (pinfunction "GND_1") (pintype "passive"))
      (node (ref "XC2") (pin "3") (pinfunction "3_3") (pintype "passive"))
      (node (ref "XC2") (pin "4") (pinfunction "4_4") (pintype "passive"))
    )
    (net (code "12") (name "Net-(C5-Pad1)") (class "Default")
      (node (ref "C5") (pin "1") (pinfunction "1_1") (pintype "passive"))
      (node (ref "R1") (pin "1") (pinfunction "1_1") (pintype "passive"))
    )
    (net (code "13") (name "Net-(C8-Pad1)") (class "Default")
      (node (ref "C8") (pin "1") (pinfunction "1_1") (pintype "passive"))
      (node (ref "R3") (pin "1") (pinfunction "1_1") (pintype "passive"))
    )
    (net (code "14") (name "Net-(C14-Pad1)") (class "Default")
      (node (ref "C14") (pin "1") (pinfunction "1_1") (pintype "passive"))
      (node (ref "K1") (pin "5") (pinfunction "5_5") (pintype "passive"))
      (node (ref "R7") (pin "1") (pinfunction "1_1") (pintype "passive"))
    )
    (net (code "15") (name "Net-(C25-Pad1)") (class "Default")
      (node (ref "C25") (pin "1") (pinfunction "1_1") (pintype "passive"))
      (node (ref "R15") (pin "1") (pinfunction "1_1") (pintype "passive"))
    )
    (net (code "16") (name "Net-(C28-Pad1)") (class "Default")
      (node (ref "C28") (pin "1") (pinfunction "1_1") (pintype "passive"))
      (node (ref "R18") (pin "1") (pinfunction "1_1") (pintype "passive"))
    )
    (net (code "17") (name "Net-(C29-Pad2)") (class "Default")
      (node (ref "C29") (pin "2") (pinfunction "2_2") (pintype "passive"))
      (node (ref "R19") (pin "2") (pinfunction "2_2") (pintype "passive"))
    )
    (net (code "18") (name "Net-(C30-Pad1)") (class "Default")
      (node (ref "C30") (pin "1") (pinfunction "1_1") (pintype "passive"))
      (node (ref "R16") (pin "2") (pinfunction "2_2") (pintype "passive"))
    )
    (net (code "19") (name "Net-(C34-Pad1)") (class "Default")
      (node (ref "C34") (pin "1") (pinfunction "1_1") (pintype "passive"))
      (node (ref "K1") (pin "4") (pinfunction "4_4") (pintype "passive"))
      (node (ref "L4") (pin "2") (pinfunction "2_2") (pintype "passive"))
      (node (ref "R22") (pin "2") (pinfunction "2_2") (pintype "passive"))
    )
    (net (code "20") (name "Net-(C37-Pad2)") (class "Default")
      (node (ref "C37") (pin "2") (pinfunction "2_2") (pintype "passive"))
      (node (ref "F2") (pin "2") (pinfunction "2_2") (pintype "passive"))
      (node (ref "K1") (pin "2") (pinfunction "2_2") (pintype "passive"))
    )
    (net (code "21") (name "Net-(D1-A)") (class "Default")
      (node (ref "C1") (pin "2") (pinfunction "2_2") (pintype "passive"))
      (node (ref "D1") (pin "2") (pinfunction "A_2") (pintype "passive"))
      (node (ref "DC_PWR1") (pin "1") (pinfunction "Vcc_1") (pintype "passive"))
    )
    (net (code "22") (name "Net-(D1-K)") (class "Default")
      (node (ref "D1") (pin "1") (pinfunction "K_1") (pintype "passive"))
      (node (ref "D2") (pin "1") (pinfunction "K_1") (pintype "passive"))
      (node (ref "F1") (pin "1") (pinfunction "1_1") (pintype "passive"))
    )
    (net (code "23") (name "Net-(D2-A)") (class "Default")
      (node (ref "C2") (pin "1") (pinfunction "1_1") (pintype "passive"))
      (node (ref "D2") (pin "2") (pinfunction "A_2") (pintype "passive"))
      (node (ref "XC1") (pin "2") (pinfunction "Vcc_2") (pintype "passive"))
    )
    (net (code "24") (name "Net-(D3-K)") (class "Default")
      (node (ref "C12") (pin "1") (pinfunction "1_1") (pintype "passive"))
      (node (ref "D3") (pin "1") (pinfunction "K_1") (pintype "passive"))
      (node (ref "F1") (pin "2") (pinfunction "2_2") (pintype "passive"))
      (node (ref "L1") (pin "1") (pinfunction "1_1") (pintype "passive"))
    )
    (net (code "25") (name "Net-(D4-K)") (class "Default")
      (node (ref "D4") (pin "1") (pinfunction "K_1") (pintype "passive"))
      (node (ref "R7") (pin "2") (pinfunction "2_2") (pintype "passive"))
    )
    (net (code "26") (name "Net-(D5-K)") (class "Default")
      (node (ref "C30") (pin "2") (pinfunction "2_2") (pintype "passive"))
      (node (ref "D5") (pin "1") (pinfunction "K_1") (pintype "passive"))
      (node (ref "IC3") (pin "8") (pinfunction "SW_8") (pintype "power_in"))
      (node (ref "L4") (pin "1") (pinfunction "1_1") (pintype "passive"))
      (node (ref "R19") (pin "1") (pinfunction "1_1") (pintype "passive"))
    )
    (net (code "27") (name "Net-(FAN1-+5V)") (class "Default")
      (node (ref "C11") (pin "1") (pinfunction "1_1") (pintype "passive"))
      (node (ref "C13") (pin "1") (pinfunction "1_1") (pintype "passive"))
      (node (ref "FAN1") (pin "2") (pinfunction "+5V_2") (pintype "passive"))
      (node (ref "R6") (pin "1") (pinfunction "1_1") (pintype "passive"))
    )
    (net (code "28") (name "Net-(IC1-AVIN)") (class "Default")
      (node (ref "C9") (pin "2") (pinfunction "2_2") (pintype "passive"))
      (node (ref "IC1") (pin "14") (pinfunction "AVIN_14") (pintype "input"))
      (node (ref "R4") (pin "2") (pinfunction "2_2") (pintype "passive"))
    )
    (net (code "29") (name "Net-(IC1-COMP)") (class "Default")
      (node (ref "IC1") (pin "4") (pinfunction "COMP_4") (pintype "passive"))
      (node (ref "R1") (pin "2") (pinfunction "2_2") (pintype "passive"))
    )
    (net (code "30") (name "Net-(IC1-FB)") (class "Default")
      (node (ref "IC1") (pin "2") (pinfunction "FB_2") (pintype "passive"))
      (node (ref "R10") (pin "1") (pinfunction "1_1") (pintype "passive"))
      (node (ref "R9") (pin "2") (pinfunction "2_2") (pintype "passive"))
    )
    (net (code "31") (name "Net-(IC1-SS{slash}TRK)") (class "Default")
      (node (ref "C15") (pin "2") (pinfunction "2_2") (pintype "passive"))
      (node (ref "IC1") (pin "1") (pinfunction "SS/TRK_1") (pintype "passive"))
    )
    (net (code "32") (name "Net-(IC1-SW)") (class "Default")
      (node (ref "IC1") (pin "8") (pinfunction "SW_8") (pintype "passive"))
      (node (ref "L2") (pin "1") (pinfunction "1_1") (pintype "passive"))
    )
    (net (code "33") (name "Net-(IC1-SYNCOUT)") (class "Default")
      (node (ref "IC1") (pin "16") (pinfunction "SYNCOUT_16") (pintype "output"))
      (node (ref "IC2") (pin "16") (pinfunction "SYNC_16") (pintype "input"))
      (node (ref "R2") (pin "1") (pinfunction "1_1") (pintype "passive"))
    )
    (net (code "34") (name "Net-(IC1-VCC)") (class "Default")
      (node (ref "C16") (pin "2") (pinfunction "2_2") (pintype "passive"))
      (node (ref "IC1") (pin "13") (pinfunction "VCC_13") (pintype "passive"))
    )
    (net (code "35") (name "Net-(IC2-AVIN)") (class "Default")
      (node (ref "C10") (pin "1") (pinfunction "1_1") (pintype "passive"))
      (node (ref "IC2") (pin "14") (pinfunction "AVIN_14") (pintype "input"))
      (node (ref "R5") (pin "2") (pinfunction "2_2") (pintype "passive"))
    )
    (net (code "36") (name "Net-(IC2-COMP)") (class "Default")
      (node (ref "IC2") (pin "4") (pinfunction "COMP_4") (pintype "passive"))
      (node (ref "R3") (pin "2") (pinfunction "2_2") (pintype "passive"))
    )
    (net (code "37") (name "Net-(IC2-FB)") (class "Default")
      (node (ref "IC2") (pin "2") (pinfunction "FB_2") (pintype "passive"))
      (node (ref "R11") (pin "2") (pinfunction "2_2") (pintype "passive"))
      (node (ref "R12") (pin "1") (pinfunction "1_1") (pintype "passive"))
    )
    (net (code "38") (name "Net-(IC2-SS{slash}TRK)") (class "Default")
      (node (ref "IC2") (pin "1") (pinfunction "SS/TRK_1") (pintype "passive"))
      (node (ref "R13") (pin "2") (pinfunction "2_2") (pintype "passive"))
      (node (ref "R8") (pin "2") (pinfunction "2_2") (pintype "passive"))
    )
    (net (code "39") (name "Net-(IC2-SW)") (class "Default")
      (node (ref "IC2") (pin "8") (pinfunction "SW_8") (pintype "passive"))
      (node (ref "L3") (pin "1") (pinfunction "1_1") (pintype "passive"))
    )
    (net (code "40") (name "Net-(IC2-VCC)") (class "Default")
      (node (ref "C17") (pin "2") (pinfunction "2_2") (pintype "passive"))
      (node (ref "IC2") (pin "13") (pinfunction "VCC_13") (pintype "passive"))
    )
    (net (code "41") (name "Net-(IC3-BOOT)") (class "Default")
      (node (ref "IC3") (pin "1") (pinfunction "BOOT_1") (pintype "input"))
      (node (ref "R16") (pin "1") (pinfunction "1_1") (pintype "passive"))
    )
    (net (code "42") (name "Net-(IC3-EN)") (class "Default")
      (node (ref "IC3") (pin "5") (pinfunction "EN_5") (pintype "input"))
      (node (ref "R14") (pin "1") (pinfunction "1_1") (pintype "passive"))
    )
    (net (code "43") (name "Net-(IC3-FB)") (class "Default")
      (node (ref "IC3") (pin "4") (pinfunction "FB_4") (pintype "input"))
      (node (ref "R22") (pin "1") (pinfunction "1_1") (pintype "passive"))
      (node (ref "R23") (pin "2") (pinfunction "2_2") (pintype "passive"))
    )
    (net (code "44") (name "Net-(IC4-AVIN)") (class "Default")
      (node (ref "C31") (pin "1") (pinfunction "1_1") (pintype "passive"))
      (node (ref "IC4") (pin "14") (pinfunction "AVIN_14") (pintype "input"))
      (node (ref "R20") (pin "2") (pinfunction "2_2") (pintype "passive"))
    )
    (net (code "45") (name "Net-(IC4-COMP)") (class "Default")
      (node (ref "IC4") (pin "4") (pinfunction "COMP_4") (pintype "passive"))
      (node (ref "R15") (pin "2") (pinfunction "2_2") (pintype "passive"))
    )
    (net (code "46") (name "Net-(IC4-FB)") (class "Default")
      (node (ref "IC4") (pin "2") (pinfunction "FB_2") (pintype "passive"))
      (node (ref "R25") (pin "2") (pinfunction "2_2") (pintype "passive"))
      (node (ref "R26") (pin "1") (pinfunction "1_1") (pintype "passive"))
    )
    (net (code "47") (name "Net-(IC4-SS{slash}TRK)") (class "Default")
      (node (ref "C33") (pin "1") (pinfunction "1_1") (pintype "passive"))
      (node (ref "IC4") (pin "1") (pinfunction "SS/TRK_1") (pintype "passive"))
    )
    (net (code "48") (name "Net-(IC4-SW)") (class "Default")
      (node (ref "IC4") (pin "8") (pinfunction "SW_8") (pintype "passive"))
      (node (ref "L5") (pin "1") (pinfunction "1_1") (pintype "passive"))
    )
    (net (code "49") (name "Net-(IC4-SYNCOUT)") (class "Default")
      (node (ref "IC4") (pin "16") (pinfunction "SYNCOUT_16") (pintype "output"))
      (node (ref "IC5") (pin "16") (pinfunction "SYNC_16") (pintype "input"))
      (node (ref "R17") (pin "2") (pinfunction "2_2") (pintype "passive"))
    )
    (net (code "50") (name "Net-(IC4-VCC)") (class "Default")
      (node (ref "C35") (pin "2") (pinfunction "2_2") (pintype "passive"))
      (node (ref "IC4") (pin "13") (pinfunction "VCC_13") (pintype "passive"))
    )
    (net (code "51") (name "Net-(IC5-AVIN)") (class "Default")
      (node (ref "C32") (pin "1") (pinfunction "1_1") (pintype "passive"))
      (node (ref "IC5") (pin "14") (pinfunction "AVIN_14") (pintype "input"))
      (node (ref "R21") (pin "2") (pinfunction "2_2") (pintype "passive"))
    )
    (net (code "52") (name "Net-(IC5-COMP)") (class "Default")
      (node (ref "IC5") (pin "4") (pinfunction "COMP_4") (pintype "passive"))
      (node (ref "R18") (pin "2") (pinfunction "2_2") (pintype "passive"))
    )
    (net (code "53") (name "Net-(IC5-FB)") (class "Default")
      (node (ref "IC5") (pin "2") (pinfunction "FB_2") (pintype "passive"))
      (node (ref "R27") (pin "2") (pinfunction "2_2") (pintype "passive"))
      (node (ref "R28") (pin "1") (pinfunction "1_1") (pintype "passive"))
    )
    (net (code "54") (name "Net-(IC5-SS{slash}TRK)") (class "Default")
      (node (ref "IC5") (pin "1") (pinfunction "SS/TRK_1") (pintype "passive"))
      (node (ref "R24") (pin "2") (pinfunction "2_2") (pintype "passive"))
      (node (ref "R29") (pin "2") (pinfunction "2_2") (pintype "passive"))
    )
    (net (code "55") (name "Net-(IC5-SW)") (class "Default")
      (node (ref "IC5") (pin "8") (pinfunction "SW_8") (pintype "passive"))
      (node (ref "L6") (pin "1") (pinfunction "1_1") (pintype "passive"))
    )
    (net (code "56") (name "Net-(IC5-VCC)") (class "Default")
      (node (ref "C36") (pin "2") (pinfunction "2_2") (pintype "passive"))
      (node (ref "IC5") (pin "13") (pinfunction "VCC_13") (pintype "passive"))
    )
    (net (code "57") (name "Net-(LED1-A)") (class "Default")
      (node (ref "LED1") (pin "2") (pinfunction "A_2") (pintype "passive"))
      (node (ref "R32") (pin "1") (pinfunction "1_1") (pintype "passive"))
    )
    (net (code "58") (name "Net-(LED1-K)") (class "Default")
      (node (ref "LED1") (pin "1") (pinfunction "K_1") (pintype "passive"))
      (node (ref "Q1") (pin "3") (pinfunction "D_3") (pintype "passive"))
    )
    (net (code "59") (name "Net-(LED2-A)") (class "Default")
      (node (ref "LED2") (pin "2") (pinfunction "A_2") (pintype "passive"))
      (node (ref "R33") (pin "1") (pinfunction "1_1") (pintype "passive"))
    )
    (net (code "60") (name "Net-(LED2-K)") (class "Default")
      (node (ref "LED2") (pin "1") (pinfunction "K_1") (pintype "passive"))
      (node (ref "Q2") (pin "3") (pinfunction "D_3") (pintype "passive"))
    )
    (net (code "61") (name "Net-(LED3-A)") (class "Default")
      (node (ref "LED3") (pin "2") (pinfunction "A_2") (pintype "passive"))
      (node (ref "R36") (pin "1") (pinfunction "1_1") (pintype "passive"))
    )
    (net (code "62") (name "Net-(LED3-K)") (class "Default")
      (node (ref "LED3") (pin "1") (pinfunction "K_1") (pintype "passive"))
      (node (ref "Q3") (pin "3") (pinfunction "D_3") (pintype "passive"))
    )
    (net (code "63") (name "Net-(LED4-A)") (class "Default")
      (node (ref "LED4") (pin "2") (pinfunction "A_2") (pintype "passive"))
      (node (ref "R37") (pin "1") (pinfunction "1_1") (pintype "passive"))
    )
    (net (code "64") (name "Net-(LED4-K)") (class "Default")
      (node (ref "LED4") (pin "1") (pinfunction "K_1") (pintype "passive"))
      (node (ref "Q4") (pin "3") (pinfunction "D_3") (pintype "passive"))
    )
    (net (code "65") (name "V_Unreg") (class "Default")
      (node (ref "C18") (pin "1") (pinfunction "1_1") (pintype "passive"))
      (node (ref "C21") (pin "1") (pinfunction "1_1") (pintype "passive"))
      (node (ref "C22") (pin "1") (pinfunction "1_1") (pintype "passive"))
      (node (ref "IC3") (pin "7") (pinfunction "VIN_7") (pintype "power_in"))
      (node (ref "L1") (pin "2") (pinfunction "2_2") (pintype "passive"))
      (node (ref "R14") (pin "2") (pinfunction "2_2") (pintype "passive"))
    )
    (net (code "66") (name "unconnected-(FAN1-NC-Pad3)") (class "Default")
      (node (ref "FAN1") (pin "3") (pinfunction "NC_3") (pintype "passive"))
    )
  )
)
